# MCU_-_AUDIO.net
KiCad netlist of a schematic drawn in Altium Designer
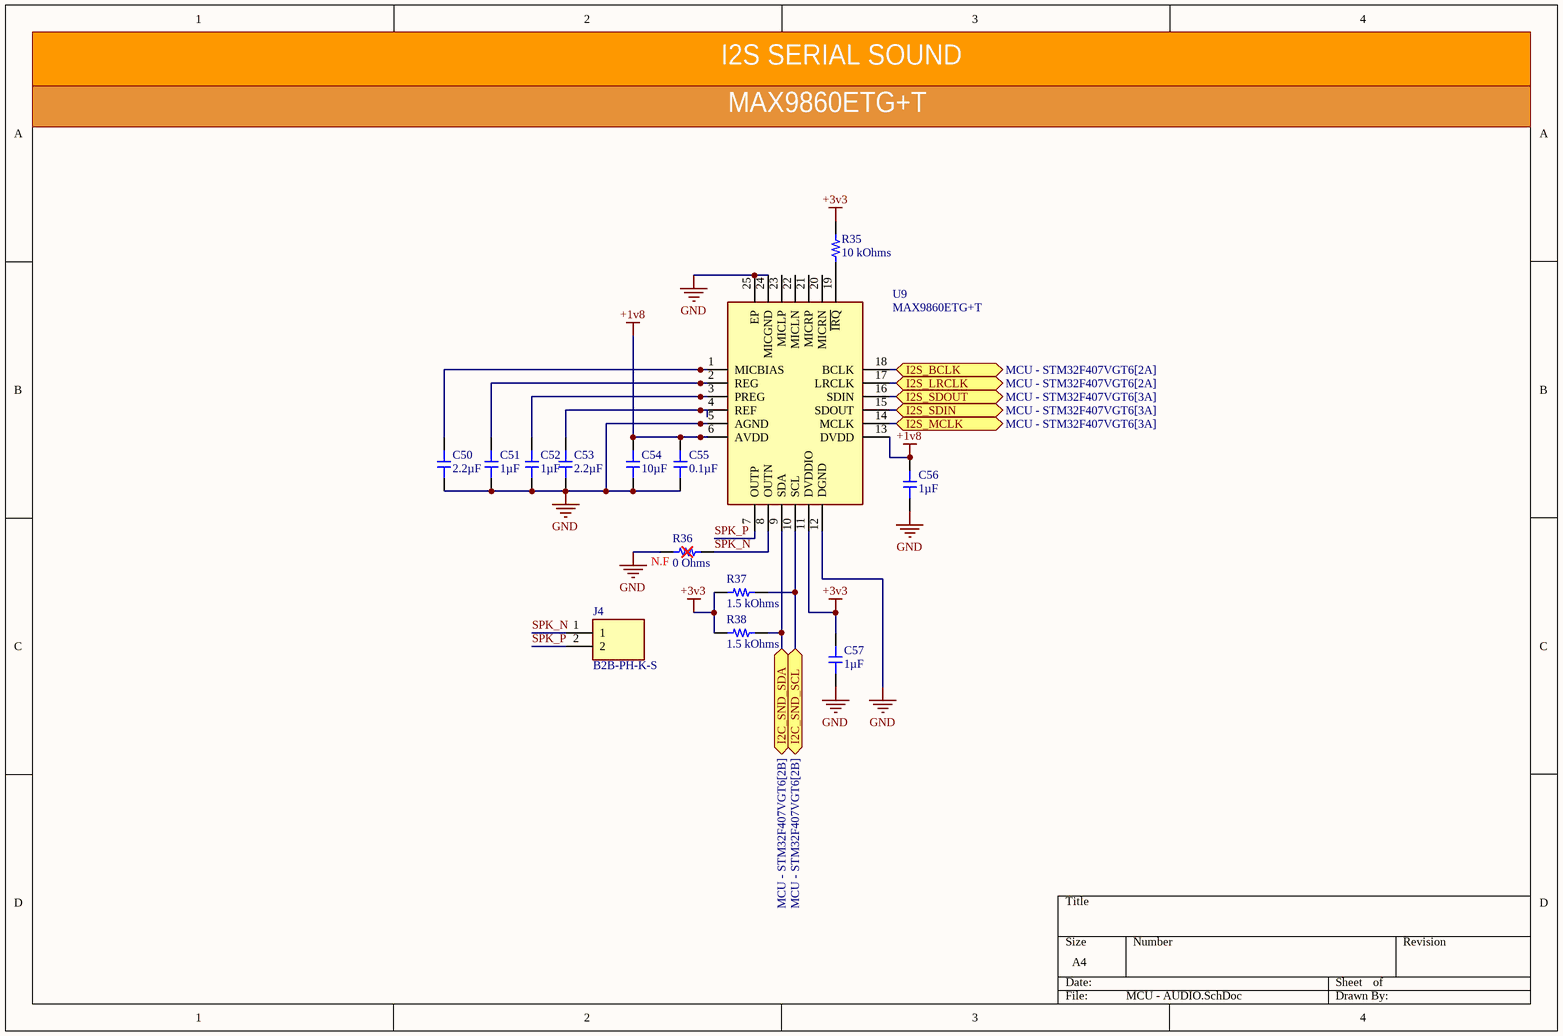
[diagram p0: MCU - AUDIO.SchDoc]

(export (version "E")
  (design (tool "Eeschema 10.0.6"))
  (components
    (comp (ref "C50")
      (value "2.2µF")
      (footprint "0603_Footprint")
      (description "2.2uF 0603 Surface Capacitor")
      (libsource (lib "ELK_H7-V2 Library") (part "2.2uF 0603 Surface Capacitor"))
    )
    (comp (ref "C51")
      (value "1µF")
      (footprint "0603_Footprint")
      (description "1uF 0603 Surface Capacitor")
      (libsource (lib "ELK_H7-V2 Library") (part "1uF 0603 Surface Capacitor"))
    )
    (comp (ref "C52")
      (value "1µF")
      (footprint "0603_Footprint")
      (description "1uF 0603 Surface Capacitor")
      (libsource (lib "ELK_H7-V2 Library") (part "1uF 0603 Surface Capacitor"))
    )
    (comp (ref "C53")
      (value "2.2µF")
      (footprint "0603_Footprint")
      (description "2.2uF 0603 Surface Capacitor")
      (libsource (lib "ELK_H7-V2 Library") (part "2.2uF 0603 Surface Capacitor"))
    )
    (comp (ref "C54")
      (value "10µF")
      (footprint "0805")
      (description "10uF 0805 Surface Capacitor")
      (libsource (lib "ELK_H7-V2 Library") (part "10uF 0805 Surface Capacitor"))
    )
    (comp (ref "C55")
      (value "0.1µF")
      (footprint "0603_Footprint")
      (description "0.1uF 0603 Surface Capacitor")
      (libsource (lib "ELK_H7-V2 Library") (part "0.1uF 0603 Surface Capacitor_1_1_1_1_1_1"))
    )
    (comp (ref "C56")
      (value "1µF")
      (footprint "0603_Footprint")
      (description "1uF 0603 Surface Capacitor")
      (libsource (lib "ELK_H7-V2 Library") (part "1uF 0603 Surface Capacitor"))
    )
    (comp (ref "C57")
      (value "1µF")
      (footprint "0603_Footprint")
      (description "1uF 0603 Surface Capacitor")
      (libsource (lib "ELK_H7-V2 Library") (part "1uF 0603 Surface Capacitor"))
    )
    (comp (ref "J4")
      (value "B2B-PH-K-S")
      (footprint "JST_B2B-PH-K-S")
      (description "Connector Header Through Hole 2 position 0.079 (2.00mm)")
      (fields (field (name "MF") "JST Sales America Inc."))
      (libsource (lib "ELK_H7-V2 Library") (part "B2B-PH-K-S"))
    )
    (comp (ref "R35")
      (value "10 kOhms")
      (footprint "0603_RES")
      (description "10 kOhms 0603")
      (libsource (lib "ELK_H7-V2 Library") (part "10 kOhms 0603"))
    )
    (comp (ref "R36")
      (value "0 Ohms")
      (footprint "0603_RES")
      (description "0 Ohm 0603")
      (libsource (lib "ELK_H7-V2 Library") (part "0 Ohm 0603"))
    )
    (comp (ref "R37")
      (value "1.5 kOhms")
      (footprint "0603_RES")
      (description "1.5 kOhms 0603")
      (libsource (lib "ELK_H7-V2 Library") (part "1.5 kOhms 0603"))
    )
    (comp (ref "R38")
      (value "1.5 kOhms")
      (footprint "0603_RES")
      (description "1.5 kOhms 0603")
      (libsource (lib "ELK_H7-V2 Library") (part "1.5 kOhms 0603"))
    )
    (comp (ref "U9")
      (value "MAX9860ETG+T")
      (footprint "QFN50P400X400X80-25N")
      (description "Integrated Circuit")
      (fields (field (name "MOUSER PART NUMBER") "700-MAX9860ETGT"))
      (libsource (lib "ELK_H7-V2 Library") (part "MAX9860ETG+T"))
    )
  )
  (nets
    (net (code "1") (name "+1v8") (class "Default")
      (node (ref "C54") (pin "1") (pinfunction "1_1") (pintype "passive"))
      (node (ref "C55") (pin "1") (pinfunction "1_1") (pintype "passive"))
      (node (ref "C56") (pin "1") (pinfunction "1_1") (pintype "passive"))
      (node (ref "U9") (pin "13") (pinfunction "DVDD_13") (pintype "passive"))
      (node (ref "U9") (pin "6") (pinfunction "AVDD_6") (pintype "passive"))
    )
    (net (code "2") (name "+3v3") (class "Default")
      (node (ref "C57") (pin "1") (pinfunction "1_1") (pintype "passive"))
      (node (ref "R35") (pin "2") (pinfunction "2_2") (pintype "passive"))
      (node (ref "R37") (pin "1") (pinfunction "1_1") (pintype "passive"))
      (node (ref "R38") (pin "1") (pinfunction "1_1") (pintype "passive"))
      (node (ref "U9") (pin "11") (pinfunction "DVDDIO_11") (pintype "passive"))
    )
    (net (code "3") (name "/I2C_SND_SCL") (class "Default")
      (node (ref "R37") (pin "2") (pinfunction "2_2") (pintype "passive"))
      (node (ref "U9") (pin "10") (pinfunction "SCL_10") (pintype "passive"))
    )
    (net (code "4") (name "/I2C_SND_SDA") (class "Default")
      (node (ref "R38") (pin "2") (pinfunction "2_2") (pintype "passive"))
      (node (ref "U9") (pin "9") (pinfunction "SDA_9") (pintype "passive"))
    )
    (net (code "5") (name "/I2S_BCLK") (class "Default")
      (node (ref "U9") (pin "18") (pinfunction "BCLK_18") (pintype "passive"))
    )
    (net (code "6") (name "/I2S_LRCLK") (class "Default")
      (node (ref "U9") (pin "17") (pinfunction "LRCLK_17") (pintype "passive"))
    )
    (net (code "7") (name "/I2S_MCLK") (class "Default")
      (node (ref "U9") (pin "14") (pinfunction "MCLK_14") (pintype "passive"))
    )
    (net (code "8") (name "/I2S_SDIN") (class "Default")
      (node (ref "U9") (pin "15") (pinfunction "SDOUT_15") (pintype "passive"))
    )
    (net (code "9") (name "/I2S_SDOUT") (class "Default")
      (node (ref "U9") (pin "16") (pinfunction "SDIN_16") (pintype "passive"))
    )
    (net (code "10") (name "/SPK_N") (class "Default")
      (node (ref "J4") (pin "1") (pinfunction "1_1") (pintype "passive"))
      (node (ref "R36") (pin "2") (pinfunction "2_2") (pintype "passive"))
      (node (ref "U9") (pin "8") (pinfunction "OUTN_8") (pintype "passive"))
    )
    (net (code "11") (name "/SPK_P") (class "Default")
      (node (ref "J4") (pin "2") (pinfunction "2_2") (pintype "passive"))
      (node (ref "U9") (pin "7") (pinfunction "OUTP_7") (pintype "passive"))
    )
    (net (code "12") (name "GND") (class "Default")
      (node (ref "C50") (pin "1") (pinfunction "1_1") (pintype "passive"))
      (node (ref "C51") (pin "2") (pinfunction "2_2") (pintype "passive"))
      (node (ref "C52") (pin "2") (pinfunction "2_2") (pintype "passive"))
      (node (ref "C53") (pin "1") (pinfunction "1_1") (pintype "passive"))
      (node (ref "C54") (pin "2") (pinfunction "2_2") (pintype "passive"))
      (node (ref "C55") (pin "2") (pinfunction "2_2") (pintype "passive"))
      (node (ref "C56") (pin "2") (pinfunction "2_2") (pintype "passive"))
      (node (ref "C57") (pin "2") (pinfunction "2_2") (pintype "passive"))
      (node (ref "R36") (pin "1") (pinfunction "1_1") (pintype "passive"))
      (node (ref "U9") (pin "12") (pinfunction "DGND_12") (pintype "passive"))
      (node (ref "U9") (pin "24") (pinfunction "MICGND_24") (pintype "passive"))
      (node (ref "U9") (pin "25") (pinfunction "EP_25") (pintype "passive"))
      (node (ref "U9") (pin "5") (pinfunction "AGND_5") (pintype "passive"))
    )
    (net (code "13") (name "Net-(U9-MICBIAS)") (class "Default")
      (node (ref "C50") (pin "2") (pinfunction "2_2") (pintype "passive"))
      (node (ref "U9") (pin "1") (pinfunction "MICBIAS_1") (pintype "passive"))
    )
    (net (code "14") (name "Net-(U9-PREG)") (class "Default")
      (node (ref "C52") (pin "1") (pinfunction "1_1") (pintype "passive"))
      (node (ref "U9") (pin "3") (pinfunction "PREG_3") (pintype "passive"))
    )
    (net (code "15") (name "Net-(U9-REF)") (class "Default")
      (node (ref "C53") (pin "2") (pinfunction "2_2") (pintype "passive"))
      (node (ref "U9") (pin "4") (pinfunction "REF_4") (pintype "passive"))
    )
    (net (code "16") (name "Net-(U9-REG)") (class "Default")
      (node (ref "C51") (pin "1") (pinfunction "1_1") (pintype "passive"))
      (node (ref "U9") (pin "2") (pinfunction "REG_2") (pintype "passive"))
    )
    (net (code "17") (name "Net-(U9-~{IRQ})") (class "Default")
      (node (ref "R35") (pin "1") (pinfunction "1_1") (pintype "passive"))
      (node (ref "U9") (pin "19") (pinfunction "~{IRQ}_19") (pintype "passive"))
    )
    (net (code "18") (name "unconnected-(U9-MICLN-Pad22)") (class "Default")
      (node (ref "U9") (pin "22") (pinfunction "MICLN_22") (pintype "passive"))
    )
    (net (code "19") (name "unconnected-(U9-MICLP-Pad23)") (class "Default")
      (node (ref "U9") (pin "23") (pinfunction "MICLP_23") (pintype "passive"))
    )
    (net (code "20") (name "unconnected-(U9-MICRN-Pad20)") (class "Default")
      (node (ref "U9") (pin "20") (pinfunction "MICRN_20") (pintype "passive"))
    )
    (net (code "21") (name "unconnected-(U9-MICRP-Pad21)") (class "Default")
      (node (ref "U9") (pin "21") (pinfunction "MICRP_21") (pintype "passive"))
    )
  )
)
